# hexapod.net
KiCad netlist of a schematic drawn in EAGLE
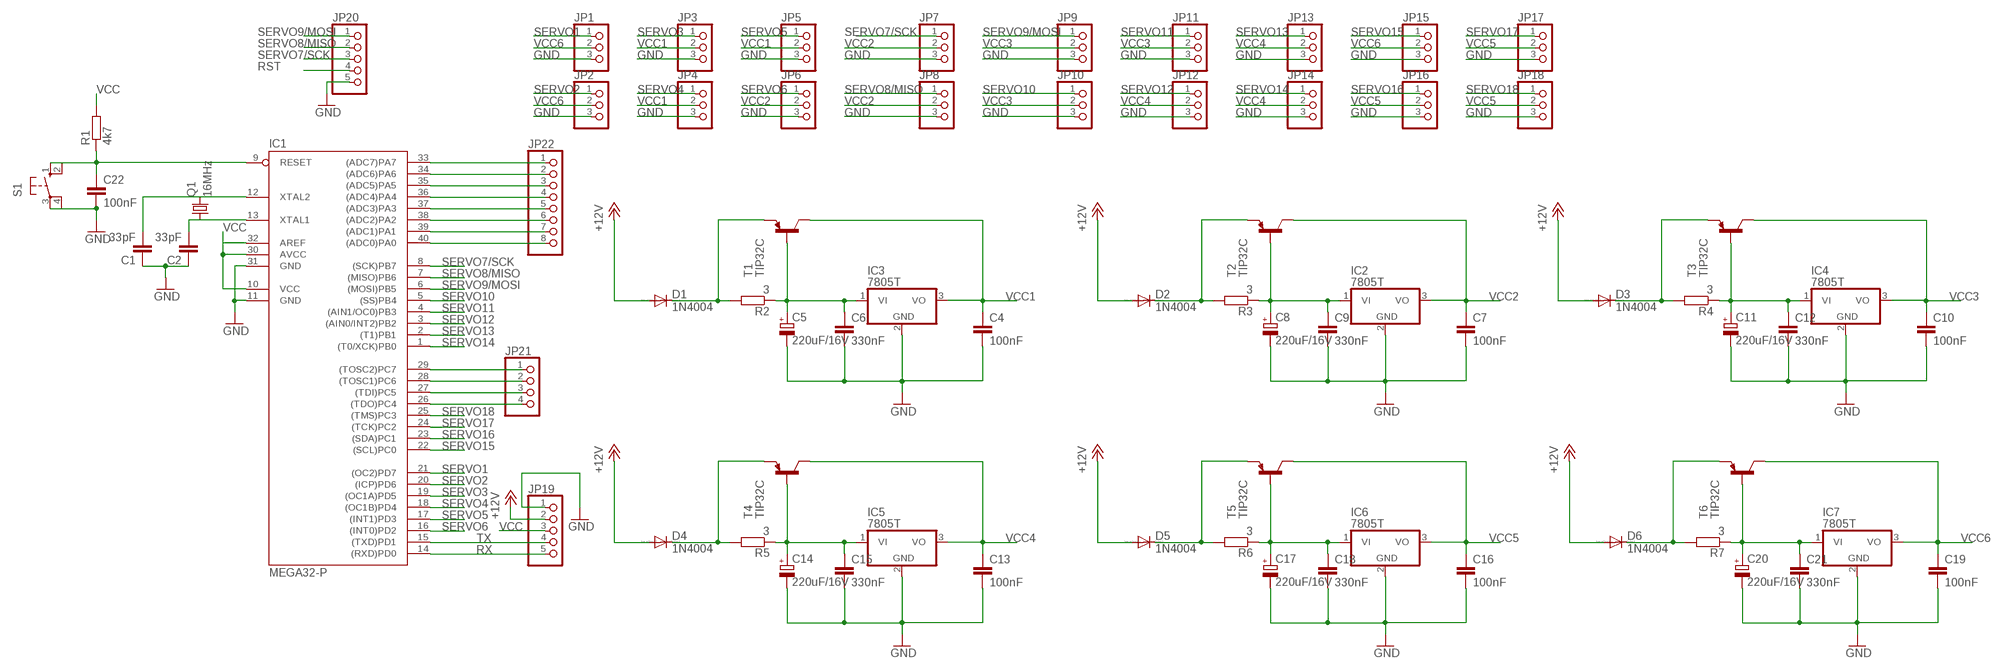
[diagram p0: schematic, sheet 1]

(export (version "E")
  (design (tool "Eeschema 10.0.6"))
  (components
    (comp (ref "C1")
      (value "33pF")
      (footprint "eagle-import:C025-025X050")
      (libsource (lib "eagle-import") (part "resistor_C-EU025-025X050"))
    )
    (comp (ref "C2")
      (value "33pF")
      (footprint "eagle-import:C025-025X050")
      (libsource (lib "eagle-import") (part "resistor_C-EU025-025X050"))
    )
    (comp (ref "C4")
      (value "100nF")
      (footprint "eagle-import:C050-025X075")
      (libsource (lib "eagle-import") (part "C-EU050-025X075"))
    )
    (comp (ref "C5")
      (value "220uF/16V")
      (footprint "eagle-import:E2,5-6E")
      (libsource (lib "eagle-import") (part "CPOL-EUE2,5-6E"))
    )
    (comp (ref "C6")
      (value "330nF")
      (footprint "eagle-import:C050-025X075")
      (libsource (lib "eagle-import") (part "C-EU050-025X075"))
    )
    (comp (ref "C7")
      (value "100nF")
      (footprint "eagle-import:C050-025X075")
      (libsource (lib "eagle-import") (part "C-EU050-025X075"))
    )
    (comp (ref "C8")
      (value "220uF/16V")
      (footprint "eagle-import:E2,5-6E")
      (libsource (lib "eagle-import") (part "CPOL-EUE2,5-6E"))
    )
    (comp (ref "C9")
      (value "330nF")
      (footprint "eagle-import:C050-025X075")
      (libsource (lib "eagle-import") (part "C-EU050-025X075"))
    )
    (comp (ref "C10")
      (value "100nF")
      (footprint "eagle-import:C050-025X075")
      (libsource (lib "eagle-import") (part "C-EU050-025X075"))
    )
    (comp (ref "C11")
      (value "220uF/16V")
      (footprint "eagle-import:E2,5-6E")
      (libsource (lib "eagle-import") (part "CPOL-EUE2,5-6E"))
    )
    (comp (ref "C12")
      (value "330nF")
      (footprint "eagle-import:C050-025X075")
      (libsource (lib "eagle-import") (part "C-EU050-025X075"))
    )
    (comp (ref "C13")
      (value "100nF")
      (footprint "eagle-import:C050-025X075")
      (libsource (lib "eagle-import") (part "C-EU050-025X075"))
    )
    (comp (ref "C14")
      (value "220uF/16V")
      (footprint "eagle-import:E2,5-6E")
      (libsource (lib "eagle-import") (part "CPOL-EUE2,5-6E"))
    )
    (comp (ref "C15")
      (value "330nF")
      (footprint "eagle-import:C050-025X075")
      (libsource (lib "eagle-import") (part "C-EU050-025X075"))
    )
    (comp (ref "C16")
      (value "100nF")
      (footprint "eagle-import:C050-025X075")
      (libsource (lib "eagle-import") (part "C-EU050-025X075"))
    )
    (comp (ref "C17")
      (value "220uF/16V")
      (footprint "eagle-import:E2,5-6E")
      (libsource (lib "eagle-import") (part "CPOL-EUE2,5-6E"))
    )
    (comp (ref "C18")
      (value "330nF")
      (footprint "eagle-import:C050-025X075")
      (libsource (lib "eagle-import") (part "C-EU050-025X075"))
    )
    (comp (ref "C19")
      (value "100nF")
      (footprint "eagle-import:C050-025X075")
      (libsource (lib "eagle-import") (part "C-EU050-025X075"))
    )
    (comp (ref "C20")
      (value "220uF/16V")
      (footprint "eagle-import:E2,5-6E")
      (libsource (lib "eagle-import") (part "CPOL-EUE2,5-6E"))
    )
    (comp (ref "C21")
      (value "330nF")
      (footprint "eagle-import:C050-025X075")
      (libsource (lib "eagle-import") (part "C-EU050-025X075"))
    )
    (comp (ref "C22")
      (value "100nF")
      (footprint "eagle-import:C050-025X075")
      (libsource (lib "eagle-import") (part "C-EU050-025X075"))
    )
    (comp (ref "D1")
      (value "1N4004")
      (footprint "eagle-import:DO41-10")
      (libsource (lib "eagle-import") (part "1N4004"))
    )
    (comp (ref "D2")
      (value "1N4004")
      (footprint "eagle-import:DO41-10")
      (libsource (lib "eagle-import") (part "1N4004"))
    )
    (comp (ref "D3")
      (value "1N4004")
      (footprint "eagle-import:DO41-10")
      (libsource (lib "eagle-import") (part "1N4004"))
    )
    (comp (ref "D4")
      (value "1N4004")
      (footprint "eagle-import:DO41-10")
      (libsource (lib "eagle-import") (part "1N4004"))
    )
    (comp (ref "D5")
      (value "1N4004")
      (footprint "eagle-import:DO41-10")
      (libsource (lib "eagle-import") (part "1N4004"))
    )
    (comp (ref "D6")
      (value "1N4004")
      (footprint "eagle-import:DO41-10")
      (libsource (lib "eagle-import") (part "1N4004"))
    )
    (comp (ref "IC1")
      (value "MEGA32-P")
      (footprint "eagle-import:DIL40")
      (fields (field (name "MPN") "ATMEGA32-16PU"))
      (libsource (lib "eagle-import") (part "MEGA32-P"))
    )
    (comp (ref "IC2")
      (value "7805T")
      (footprint "eagle-import:TO220H")
      (libsource (lib "eagle-import") (part "78T05"))
    )
    (comp (ref "IC3")
      (value "7805T")
      (footprint "eagle-import:TO220H")
      (libsource (lib "eagle-import") (part "78T05"))
    )
    (comp (ref "IC4")
      (value "7805T")
      (footprint "eagle-import:TO220H")
      (libsource (lib "eagle-import") (part "78T05"))
    )
    (comp (ref "IC5")
      (value "7805T")
      (footprint "eagle-import:TO220H")
      (libsource (lib "eagle-import") (part "78T05"))
    )
    (comp (ref "IC6")
      (value "7805T")
      (footprint "eagle-import:TO220H")
      (libsource (lib "eagle-import") (part "78T05"))
    )
    (comp (ref "IC7")
      (value "7805T")
      (footprint "eagle-import:TO220H")
      (libsource (lib "eagle-import") (part "78T05"))
    )
    (comp (ref "JP1")
      (value "PINHD-1X3")
      (footprint "eagle-import:1X03")
      (libsource (lib "eagle-import") (part "PINHD-1X3"))
    )
    (comp (ref "JP2")
      (value "PINHD-1X3")
      (footprint "eagle-import:1X03")
      (libsource (lib "eagle-import") (part "PINHD-1X3"))
    )
    (comp (ref "JP3")
      (value "PINHD-1X3")
      (footprint "eagle-import:1X03")
      (libsource (lib "eagle-import") (part "PINHD-1X3"))
    )
    (comp (ref "JP4")
      (value "PINHD-1X3")
      (footprint "eagle-import:1X03")
      (libsource (lib "eagle-import") (part "PINHD-1X3"))
    )
    (comp (ref "JP5")
      (value "PINHD-1X3")
      (footprint "eagle-import:1X03")
      (libsource (lib "eagle-import") (part "PINHD-1X3"))
    )
    (comp (ref "JP6")
      (value "PINHD-1X3")
      (footprint "eagle-import:1X03")
      (libsource (lib "eagle-import") (part "PINHD-1X3"))
    )
    (comp (ref "JP7")
      (value "PINHD-1X3")
      (footprint "eagle-import:1X03")
      (libsource (lib "eagle-import") (part "PINHD-1X3"))
    )
    (comp (ref "JP8")
      (value "PINHD-1X3")
      (footprint "eagle-import:1X03")
      (libsource (lib "eagle-import") (part "PINHD-1X3"))
    )
    (comp (ref "JP9")
      (value "PINHD-1X3")
      (footprint "eagle-import:1X03")
      (libsource (lib "eagle-import") (part "PINHD-1X3"))
    )
    (comp (ref "JP10")
      (value "PINHD-1X3")
      (footprint "eagle-import:1X03")
      (libsource (lib "eagle-import") (part "PINHD-1X3"))
    )
    (comp (ref "JP11")
      (value "PINHD-1X3")
      (footprint "eagle-import:1X03")
      (libsource (lib "eagle-import") (part "PINHD-1X3"))
    )
    (comp (ref "JP12")
      (value "PINHD-1X3")
      (footprint "eagle-import:1X03")
      (libsource (lib "eagle-import") (part "PINHD-1X3"))
    )
    (comp (ref "JP13")
      (value "PINHD-1X3")
      (footprint "eagle-import:1X03")
      (libsource (lib "eagle-import") (part "PINHD-1X3"))
    )
    (comp (ref "JP14")
      (value "PINHD-1X3")
      (footprint "eagle-import:1X03")
      (libsource (lib "eagle-import") (part "PINHD-1X3"))
    )
    (comp (ref "JP15")
      (value "PINHD-1X3")
      (footprint "eagle-import:1X03")
      (libsource (lib "eagle-import") (part "PINHD-1X3"))
    )
    (comp (ref "JP16")
      (value "PINHD-1X3")
      (footprint "eagle-import:1X03")
      (libsource (lib "eagle-import") (part "PINHD-1X3"))
    )
    (comp (ref "JP17")
      (value "PINHD-1X3")
      (footprint "eagle-import:1X03")
      (libsource (lib "eagle-import") (part "PINHD-1X3"))
    )
    (comp (ref "JP18")
      (value "PINHD-1X3")
      (footprint "eagle-import:1X03")
      (libsource (lib "eagle-import") (part "PINHD-1X3"))
    )
    (comp (ref "JP19")
      (value "PINHD-1X5")
      (footprint "eagle-import:1X05")
      (libsource (lib "eagle-import") (part "PINHD-1X5"))
    )
    (comp (ref "JP20")
      (value "PINHD-1X5")
      (footprint "eagle-import:1X05")
      (libsource (lib "eagle-import") (part "PINHD-1X5"))
    )
    (comp (ref "JP21")
      (value "PINHD-1X4")
      (footprint "eagle-import:1X04")
      (libsource (lib "eagle-import") (part "PINHD-1X4"))
    )
    (comp (ref "JP22")
      (value "PINHD-1X8")
      (footprint "eagle-import:1X08")
      (libsource (lib "eagle-import") (part "PINHD-1X8"))
    )
    (comp (ref "Q1")
      (value "16MHz")
      (footprint "eagle-import:HC49_S")
      (libsource (lib "eagle-import") (part "CRYSTALHC49S"))
    )
    (comp (ref "R1")
      (value "4k7")
      (footprint "eagle-import:0204_7")
      (libsource (lib "eagle-import") (part "R-EU_0204/7"))
    )
    (comp (ref "R2")
      (value "3")
      (footprint "eagle-import:0204_7")
      (libsource (lib "eagle-import") (part "R-EU_0204/7"))
    )
    (comp (ref "R3")
      (value "3")
      (footprint "eagle-import:0204_7")
      (libsource (lib "eagle-import") (part "R-EU_0204/7"))
    )
    (comp (ref "R4")
      (value "3")
      (footprint "eagle-import:0204_7")
      (libsource (lib "eagle-import") (part "R-EU_0204/7"))
    )
    (comp (ref "R5")
      (value "3")
      (footprint "eagle-import:0204_7")
      (libsource (lib "eagle-import") (part "R-EU_0204/7"))
    )
    (comp (ref "R6")
      (value "3")
      (footprint "eagle-import:0204_7")
      (libsource (lib "eagle-import") (part "R-EU_0204/7"))
    )
    (comp (ref "R7")
      (value "3")
      (footprint "eagle-import:0204_7")
      (libsource (lib "eagle-import") (part "R-EU_0204/7"))
    )
    (comp (ref "S1")
      (value "10-XX")
      (footprint "eagle-import:B3F-10XX")
      (fields (field (name "MPN") "B3F-1000"))
      (libsource (lib "eagle-import") (part "10-XX"))
    )
    (comp (ref "T1")
      (value "TIP32C")
      (footprint "eagle-import:TO220")
      (libsource (lib "eagle-import") (part "TIP32C"))
    )
    (comp (ref "T2")
      (value "TIP32C")
      (footprint "eagle-import:TO220")
      (libsource (lib "eagle-import") (part "TIP32C"))
    )
    (comp (ref "T3")
      (value "TIP32C")
      (footprint "eagle-import:TO220")
      (libsource (lib "eagle-import") (part "TIP32C"))
    )
    (comp (ref "T4")
      (value "TIP32C")
      (footprint "eagle-import:TO220")
      (libsource (lib "eagle-import") (part "TIP32C"))
    )
    (comp (ref "T5")
      (value "TIP32C")
      (footprint "eagle-import:TO220")
      (libsource (lib "eagle-import") (part "TIP32C"))
    )
    (comp (ref "T6")
      (value "TIP32C")
      (footprint "eagle-import:TO220")
      (libsource (lib "eagle-import") (part "TIP32C"))
    )
  )
  (nets
    (net (code "1") (name "+12V") (class "Default")
      (node (ref "D1") (pin "A") (pinfunction "A_A") (pintype "passive"))
      (node (ref "D2") (pin "A") (pinfunction "A_A") (pintype "passive"))
      (node (ref "D3") (pin "A") (pinfunction "A_A") (pintype "passive"))
      (node (ref "D4") (pin "A") (pinfunction "A_A") (pintype "passive"))
      (node (ref "D5") (pin "A") (pinfunction "A_A") (pintype "passive"))
      (node (ref "D6") (pin "A") (pinfunction "A_A") (pintype "passive"))
      (node (ref "JP19") (pin "2") (pinfunction "2_2") (pintype "passive"))
    )
    (net (code "2") (name "/RST") (class "Default")
      (node (ref "C22") (pin "1") (pinfunction "1_1") (pintype "passive"))
      (node (ref "IC1") (pin "9") (pinfunction "RESET_9") (pintype "input"))
      (node (ref "JP20") (pin "4") (pinfunction "4_4") (pintype "passive"))
      (node (ref "R1") (pin "1") (pinfunction "1_1") (pintype "passive"))
      (node (ref "S1") (pin "1") (pinfunction "S_1") (pintype "passive"))
      (node (ref "S1") (pin "2") (pinfunction "S1_2") (pintype "passive"))
    )
    (net (code "3") (name "/RX") (class "Default")
      (node (ref "IC1") (pin "14") (pinfunction "(RXD)PD0_14") (pintype "bidirectional"))
      (node (ref "JP19") (pin "5") (pinfunction "5_5") (pintype "passive"))
    )
    (net (code "4") (name "/SERVO1") (class "Default")
      (node (ref "IC1") (pin "21") (pinfunction "(OC2)PD7_21") (pintype "bidirectional"))
      (node (ref "JP1") (pin "1") (pinfunction "1_1") (pintype "passive"))
    )
    (net (code "5") (name "/SERVO2") (class "Default")
      (node (ref "IC1") (pin "20") (pinfunction "(ICP)PD6_20") (pintype "bidirectional"))
      (node (ref "JP2") (pin "1") (pinfunction "1_1") (pintype "passive"))
    )
    (net (code "6") (name "/SERVO3") (class "Default")
      (node (ref "IC1") (pin "19") (pinfunction "(OC1A)PD5_19") (pintype "bidirectional"))
      (node (ref "JP3") (pin "1") (pinfunction "1_1") (pintype "passive"))
    )
    (net (code "7") (name "/SERVO4") (class "Default")
      (node (ref "IC1") (pin "18") (pinfunction "(OC1B)PD4_18") (pintype "bidirectional"))
      (node (ref "JP4") (pin "1") (pinfunction "1_1") (pintype "passive"))
    )
    (net (code "8") (name "/SERVO5") (class "Default")
      (node (ref "IC1") (pin "17") (pinfunction "(INT1)PD3_17") (pintype "bidirectional"))
      (node (ref "JP5") (pin "1") (pinfunction "1_1") (pintype "passive"))
    )
    (net (code "9") (name "/SERVO6") (class "Default")
      (node (ref "IC1") (pin "16") (pinfunction "(INT0)PD2_16") (pintype "bidirectional"))
      (node (ref "JP6") (pin "1") (pinfunction "1_1") (pintype "passive"))
    )
    (net (code "10") (name "/SERVO7{slash}SCK") (class "Default")
      (node (ref "IC1") (pin "8") (pinfunction "(SCK)PB7_8") (pintype "bidirectional"))
      (node (ref "JP20") (pin "3") (pinfunction "3_3") (pintype "passive"))
      (node (ref "JP7") (pin "1") (pinfunction "1_1") (pintype "passive"))
    )
    (net (code "11") (name "/SERVO8{slash}MISO") (class "Default")
      (node (ref "IC1") (pin "7") (pinfunction "(MISO)PB6_7") (pintype "bidirectional"))
      (node (ref "JP20") (pin "2") (pinfunction "2_2") (pintype "passive"))
      (node (ref "JP8") (pin "1") (pinfunction "1_1") (pintype "passive"))
    )
    (net (code "12") (name "/SERVO9{slash}MOSI") (class "Default")
      (node (ref "IC1") (pin "6") (pinfunction "(MOSI)PB5_6") (pintype "bidirectional"))
      (node (ref "JP20") (pin "1") (pinfunction "1_1") (pintype "passive"))
      (node (ref "JP9") (pin "1") (pinfunction "1_1") (pintype "passive"))
    )
    (net (code "13") (name "/SERVO10") (class "Default")
      (node (ref "IC1") (pin "5") (pinfunction "(SS)PB4_5") (pintype "bidirectional"))
      (node (ref "JP10") (pin "1") (pinfunction "1_1") (pintype "passive"))
    )
    (net (code "14") (name "/SERVO11") (class "Default")
      (node (ref "IC1") (pin "4") (pinfunction "(AIN1/OC0)PB3_4") (pintype "bidirectional"))
      (node (ref "JP11") (pin "1") (pinfunction "1_1") (pintype "passive"))
    )
    (net (code "15") (name "/SERVO12") (class "Default")
      (node (ref "IC1") (pin "3") (pinfunction "(AIN0/INT2)PB2_3") (pintype "bidirectional"))
      (node (ref "JP12") (pin "1") (pinfunction "1_1") (pintype "passive"))
    )
    (net (code "16") (name "/SERVO13") (class "Default")
      (node (ref "IC1") (pin "2") (pinfunction "(T1)PB1_2") (pintype "bidirectional"))
      (node (ref "JP13") (pin "1") (pinfunction "1_1") (pintype "passive"))
    )
    (net (code "17") (name "/SERVO14") (class "Default")
      (node (ref "IC1") (pin "1") (pinfunction "(T0/XCK)PB0_1") (pintype "bidirectional"))
      (node (ref "JP14") (pin "1") (pinfunction "1_1") (pintype "passive"))
    )
    (net (code "18") (name "/SERVO15") (class "Default")
      (node (ref "IC1") (pin "22") (pinfunction "(SCL)PC0_22") (pintype "bidirectional"))
      (node (ref "JP15") (pin "1") (pinfunction "1_1") (pintype "passive"))
    )
    (net (code "19") (name "/SERVO16") (class "Default")
      (node (ref "IC1") (pin "23") (pinfunction "(SDA)PC1_23") (pintype "bidirectional"))
      (node (ref "JP16") (pin "1") (pinfunction "1_1") (pintype "passive"))
    )
    (net (code "20") (name "/SERVO17") (class "Default")
      (node (ref "IC1") (pin "24") (pinfunction "(TCK)PC2_24") (pintype "bidirectional"))
      (node (ref "JP17") (pin "1") (pinfunction "1_1") (pintype "passive"))
    )
    (net (code "21") (name "/SERVO18") (class "Default")
      (node (ref "IC1") (pin "25") (pinfunction "(TMS)PC3_25") (pintype "bidirectional"))
      (node (ref "JP18") (pin "1") (pinfunction "1_1") (pintype "passive"))
    )
    (net (code "22") (name "/TX") (class "Default")
      (node (ref "IC1") (pin "15") (pinfunction "(TXD)PD1_15") (pintype "bidirectional"))
      (node (ref "JP19") (pin "4") (pinfunction "4_4") (pintype "passive"))
    )
    (net (code "23") (name "/VCC") (class "Default")
      (node (ref "IC1") (pin "10") (pinfunction "VCC_10") (pintype "power_in"))
      (node (ref "IC1") (pin "30") (pinfunction "AVCC_30") (pintype "power_in"))
      (node (ref "IC1") (pin "32") (pinfunction "AREF_32") (pintype "passive"))
      (node (ref "JP19") (pin "3") (pinfunction "3_3") (pintype "passive"))
      (node (ref "R1") (pin "2") (pinfunction "2_2") (pintype "passive"))
    )
    (net (code "24") (name "/VCC1") (class "Default")
      (node (ref "C4") (pin "1") (pinfunction "1_1") (pintype "passive"))
      (node (ref "IC3") (pin "3") (pinfunction "VO_3") (pintype "passive"))
      (node (ref "JP3") (pin "2") (pinfunction "2_2") (pintype "passive"))
      (node (ref "JP4") (pin "2") (pinfunction "2_2") (pintype "passive"))
      (node (ref "JP5") (pin "2") (pinfunction "2_2") (pintype "passive"))
      (node (ref "T1") (pin "2") (pinfunction "C_2") (pintype "passive"))
    )
    (net (code "25") (name "/VCC2") (class "Default")
      (node (ref "C7") (pin "1") (pinfunction "1_1") (pintype "passive"))
      (node (ref "IC2") (pin "3") (pinfunction "VO_3") (pintype "passive"))
      (node (ref "JP6") (pin "2") (pinfunction "2_2") (pintype "passive"))
      (node (ref "JP7") (pin "2") (pinfunction "2_2") (pintype "passive"))
      (node (ref "JP8") (pin "2") (pinfunction "2_2") (pintype "passive"))
      (node (ref "T2") (pin "2") (pinfunction "C_2") (pintype "passive"))
    )
    (net (code "26") (name "/VCC3") (class "Default")
      (node (ref "C10") (pin "1") (pinfunction "1_1") (pintype "passive"))
      (node (ref "IC4") (pin "3") (pinfunction "VO_3") (pintype "passive"))
      (node (ref "JP10") (pin "2") (pinfunction "2_2") (pintype "passive"))
      (node (ref "JP11") (pin "2") (pinfunction "2_2") (pintype "passive"))
      (node (ref "JP9") (pin "2") (pinfunction "2_2") (pintype "passive"))
      (node (ref "T3") (pin "2") (pinfunction "C_2") (pintype "passive"))
    )
    (net (code "27") (name "/VCC4") (class "Default")
      (node (ref "C13") (pin "1") (pinfunction "1_1") (pintype "passive"))
      (node (ref "IC5") (pin "3") (pinfunction "VO_3") (pintype "passive"))
      (node (ref "JP12") (pin "2") (pinfunction "2_2") (pintype "passive"))
      (node (ref "JP13") (pin "2") (pinfunction "2_2") (pintype "passive"))
      (node (ref "JP14") (pin "2") (pinfunction "2_2") (pintype "passive"))
      (node (ref "T4") (pin "2") (pinfunction "C_2") (pintype "passive"))
    )
    (net (code "28") (name "/VCC5") (class "Default")
      (node (ref "C16") (pin "1") (pinfunction "1_1") (pintype "passive"))
      (node (ref "IC6") (pin "3") (pinfunction "VO_3") (pintype "passive"))
      (node (ref "JP16") (pin "2") (pinfunction "2_2") (pintype "passive"))
      (node (ref "JP17") (pin "2") (pinfunction "2_2") (pintype "passive"))
      (node (ref "JP18") (pin "2") (pinfunction "2_2") (pintype "passive"))
      (node (ref "T5") (pin "2") (pinfunction "C_2") (pintype "passive"))
    )
    (net (code "29") (name "/VCC6") (class "Default")
      (node (ref "C19") (pin "1") (pinfunction "1_1") (pintype "passive"))
      (node (ref "IC7") (pin "3") (pinfunction "VO_3") (pintype "passive"))
      (node (ref "JP1") (pin "2") (pinfunction "2_2") (pintype "passive"))
      (node (ref "JP15") (pin "2") (pinfunction "2_2") (pintype "passive"))
      (node (ref "JP2") (pin "2") (pinfunction "2_2") (pintype "passive"))
      (node (ref "T6") (pin "2") (pinfunction "C_2") (pintype "passive"))
    )
    (net (code "30") (name "GND") (class "Default")
      (node (ref "C1") (pin "1") (pinfunction "1_1") (pintype "passive"))
      (node (ref "C10") (pin "2") (pinfunction "2_2") (pintype "passive"))
      (node (ref "C11") (pin "-") (pinfunction "-_-") (pintype "passive"))
      (node (ref "C12") (pin "2") (pinfunction "2_2") (pintype "passive"))
      (node (ref "C13") (pin "2") (pinfunction "2_2") (pintype "passive"))
      (node (ref "C14") (pin "-") (pinfunction "-_-") (pintype "passive"))
      (node (ref "C15") (pin "2") (pinfunction "2_2") (pintype "passive"))
      (node (ref "C16") (pin "2") (pinfunction "2_2") (pintype "passive"))
      (node (ref "C17") (pin "-") (pinfunction "-_-") (pintype "passive"))
      (node (ref "C18") (pin "2") (pinfunction "2_2") (pintype "passive"))
      (node (ref "C19") (pin "2") (pinfunction "2_2") (pintype "passive"))
      (node (ref "C2") (pin "1") (pinfunction "1_1") (pintype "passive"))
      (node (ref "C20") (pin "-") (pinfunction "-_-") (pintype "passive"))
      (node (ref "C21") (pin "2") (pinfunction "2_2") (pintype "passive"))
      (node (ref "C22") (pin "2") (pinfunction "2_2") (pintype "passive"))
      (node (ref "C4") (pin "2") (pinfunction "2_2") (pintype "passive"))
      (node (ref "C5") (pin "-") (pinfunction "-_-") (pintype "passive"))
      (node (ref "C6") (pin "2") (pinfunction "2_2") (pintype "passive"))
      (node (ref "C7") (pin "2") (pinfunction "2_2") (pintype "passive"))
      (node (ref "C8") (pin "-") (pinfunction "-_-") (pintype "passive"))
      (node (ref "C9") (pin "2") (pinfunction "2_2") (pintype "passive"))
      (node (ref "IC1") (pin "11") (pinfunction "GND_11") (pintype "power_in"))
      (node (ref "IC1") (pin "31") (pinfunction "GND_31") (pintype "power_in"))
      (node (ref "IC2") (pin "2") (pinfunction "GND_2") (pintype "passive"))
      (node (ref "IC3") (pin "2") (pinfunction "GND_2") (pintype "passive"))
      (node (ref "IC4") (pin "2") (pinfunction "GND_2") (pintype "passive"))
      (node (ref "IC5") (pin "2") (pinfunction "GND_2") (pintype "passive"))
      (node (ref "IC6") (pin "2") (pinfunction "GND_2") (pintype "passive"))
      (node (ref "IC7") (pin "2") (pinfunction "GND_2") (pintype "passive"))
      (node (ref "JP1") (pin "3") (pinfunction "3_3") (pintype "passive"))
      (node (ref "JP10") (pin "3") (pinfunction "3_3") (pintype "passive"))
      (node (ref "JP11") (pin "3") (pinfunction "3_3") (pintype "passive"))
      (node (ref "JP12") (pin "3") (pinfunction "3_3") (pintype "passive"))
      (node (ref "JP13") (pin "3") (pinfunction "3_3") (pintype "passive"))
      (node (ref "JP14") (pin "3") (pinfunction "3_3") (pintype "passive"))
      (node (ref "JP15") (pin "3") (pinfunction "3_3") (pintype "passive"))
      (node (ref "JP16") (pin "3") (pinfunction "3_3") (pintype "passive"))
      (node (ref "JP17") (pin "3") (pinfunction "3_3") (pintype "passive"))
      (node (ref "JP18") (pin "3") (pinfunction "3_3") (pintype "passive"))
      (node (ref "JP19") (pin "1") (pinfunction "1_1") (pintype "passive"))
      (node (ref "JP2") (pin "3") (pinfunction "3_3") (pintype "passive"))
      (node (ref "JP20") (pin "5") (pinfunction "5_5") (pintype "passive"))
      (node (ref "JP3") (pin "3") (pinfunction "3_3") (pintype "passive"))
      (node (ref "JP4") (pin "3") (pinfunction "3_3") (pintype "passive"))
      (node (ref "JP5") (pin "3") (pinfunction "3_3") (pintype "passive"))
      (node (ref "JP6") (pin "3") (pinfunction "3_3") (pintype "passive"))
      (node (ref "JP7") (pin "3") (pinfunction "3_3") (pintype "passive"))
      (node (ref "JP8") (pin "3") (pinfunction "3_3") (pintype "passive"))
      (node (ref "JP9") (pin "3") (pinfunction "3_3") (pintype "passive"))
      (node (ref "S1") (pin "3") (pinfunction "P_3") (pintype "passive"))
      (node (ref "S1") (pin "4") (pinfunction "P1_4") (pintype "passive"))
    )
    (net (code "31") (name "Net-(IC1-(ADC0)PA0)") (class "Default")
      (node (ref "IC1") (pin "40") (pinfunction "(ADC0)PA0_40") (pintype "bidirectional"))
      (node (ref "JP22") (pin "8") (pinfunction "8_8") (pintype "passive"))
    )
    (net (code "32") (name "Net-(IC1-(ADC1)PA1)") (class "Default")
      (node (ref "IC1") (pin "39") (pinfunction "(ADC1)PA1_39") (pintype "bidirectional"))
      (node (ref "JP22") (pin "7") (pinfunction "7_7") (pintype "passive"))
    )
    (net (code "33") (name "Net-(IC1-(ADC2)PA2)") (class "Default")
      (node (ref "IC1") (pin "38") (pinfunction "(ADC2)PA2_38") (pintype "bidirectional"))
      (node (ref "JP22") (pin "6") (pinfunction "6_6") (pintype "passive"))
    )
    (net (code "34") (name "Net-(IC1-(ADC3)PA3)") (class "Default")
      (node (ref "IC1") (pin "37") (pinfunction "(ADC3)PA3_37") (pintype "bidirectional"))
      (node (ref "JP22") (pin "5") (pinfunction "5_5") (pintype "passive"))
    )
    (net (code "35") (name "Net-(IC1-(ADC4)PA4)") (class "Default")
      (node (ref "IC1") (pin "36") (pinfunction "(ADC4)PA4_36") (pintype "bidirectional"))
      (node (ref "JP22") (pin "4") (pinfunction "4_4") (pintype "passive"))
    )
    (net (code "36") (name "Net-(IC1-(ADC5)PA5)") (class "Default")
      (node (ref "IC1") (pin "35") (pinfunction "(ADC5)PA5_35") (pintype "bidirectional"))
      (node (ref "JP22") (pin "3") (pinfunction "3_3") (pintype "passive"))
    )
    (net (code "37") (name "Net-(IC1-(ADC6)PA6)") (class "Default")
      (node (ref "IC1") (pin "34") (pinfunction "(ADC6)PA6_34") (pintype "bidirectional"))
      (node (ref "JP22") (pin "2") (pinfunction "2_2") (pintype "passive"))
    )
    (net (code "38") (name "Net-(IC1-(ADC7)PA7)") (class "Default")
      (node (ref "IC1") (pin "33") (pinfunction "(ADC7)PA7_33") (pintype "bidirectional"))
      (node (ref "JP22") (pin "1") (pinfunction "1_1") (pintype "passive"))
    )
    (net (code "39") (name "Net-(IC1-(TDI)PC5)") (class "Default")
      (node (ref "IC1") (pin "27") (pinfunction "(TDI)PC5_27") (pintype "bidirectional"))
      (node (ref "JP21") (pin "3") (pinfunction "3_3") (pintype "passive"))
    )
    (net (code "40") (name "Net-(IC1-(TDO)PC4)") (class "Default")
      (node (ref "IC1") (pin "26") (pinfunction "(TDO)PC4_26") (pintype "bidirectional"))
      (node (ref "JP21") (pin "4") (pinfunction "4_4") (pintype "passive"))
    )
    (net (code "41") (name "Net-(IC1-(TOSC1)PC6)") (class "Default")
      (node (ref "IC1") (pin "28") (pinfunction "(TOSC1)PC6_28") (pintype "bidirectional"))
      (node (ref "JP21") (pin "2") (pinfunction "2_2") (pintype "passive"))
    )
    (net (code "42") (name "Net-(IC1-(TOSC2)PC7)") (class "Default")
      (node (ref "IC1") (pin "29") (pinfunction "(TOSC2)PC7_29") (pintype "bidirectional"))
      (node (ref "JP21") (pin "1") (pinfunction "1_1") (pintype "passive"))
    )
    (net (code "43") (name "Net-(IC1-XTAL1)") (class "Default")
      (node (ref "C2") (pin "2") (pinfunction "2_2") (pintype "passive"))
      (node (ref "IC1") (pin "13") (pinfunction "XTAL1_13") (pintype "bidirectional"))
      (node (ref "Q1") (pin "1") (pinfunction "1_1") (pintype "passive"))
    )
    (net (code "44") (name "Net-(IC1-XTAL2)") (class "Default")
      (node (ref "C1") (pin "2") (pinfunction "2_2") (pintype "passive"))
      (node (ref "IC1") (pin "12") (pinfunction "XTAL2_12") (pintype "bidirectional"))
      (node (ref "Q1") (pin "2") (pinfunction "2_2") (pintype "passive"))
    )
    (net (code "45") (name "Net-(IC2-VI)") (class "Default")
      (node (ref "C8") (pin "+") (pinfunction "+_+") (pintype "passive"))
      (node (ref "C9") (pin "1") (pinfunction "1_1") (pintype "passive"))
      (node (ref "IC2") (pin "1") (pinfunction "VI_1") (pintype "input"))
      (node (ref "R3") (pin "1") (pinfunction "1_1") (pintype "passive"))
      (node (ref "T2") (pin "1") (pinfunction "B_1") (pintype "passive"))
    )
    (net (code "46") (name "Net-(IC3-VI)") (class "Default")
      (node (ref "C5") (pin "+") (pinfunction "+_+") (pintype "passive"))
      (node (ref "C6") (pin "1") (pinfunction "1_1") (pintype "passive"))
      (node (ref "IC3") (pin "1") (pinfunction "VI_1") (pintype "input"))
      (node (ref "R2") (pin "1") (pinfunction "1_1") (pintype "passive"))
      (node (ref "T1") (pin "1") (pinfunction "B_1") (pintype "passive"))
    )
    (net (code "47") (name "Net-(IC4-VI)") (class "Default")
      (node (ref "C11") (pin "+") (pinfunction "+_+") (pintype "passive"))
      (node (ref "C12") (pin "1") (pinfunction "1_1") (pintype "passive"))
      (node (ref "IC4") (pin "1") (pinfunction "VI_1") (pintype "input"))
      (node (ref "R4") (pin "1") (pinfunction "1_1") (pintype "passive"))
      (node (ref "T3") (pin "1") (pinfunction "B_1") (pintype "passive"))
    )
    (net (code "48") (name "Net-(IC5-VI)") (class "Default")
      (node (ref "C14") (pin "+") (pinfunction "+_+") (pintype "passive"))
      (node (ref "C15") (pin "1") (pinfunction "1_1") (pintype "passive"))
      (node (ref "IC5") (pin "1") (pinfunction "VI_1") (pintype "input"))
      (node (ref "R5") (pin "1") (pinfunction "1_1") (pintype "passive"))
      (node (ref "T4") (pin "1") (pinfunction "B_1") (pintype "passive"))
    )
    (net (code "49") (name "Net-(IC6-VI)") (class "Default")
      (node (ref "C17") (pin "+") (pinfunction "+_+") (pintype "passive"))
      (node (ref "C18") (pin "1") (pinfunction "1_1") (pintype "passive"))
      (node (ref "IC6") (pin "1") (pinfunction "VI_1") (pintype "input"))
      (node (ref "R6") (pin "1") (pinfunction "1_1") (pintype "passive"))
      (node (ref "T5") (pin "1") (pinfunction "B_1") (pintype "passive"))
    )
    (net (code "50") (name "Net-(IC7-VI)") (class "Default")
      (node (ref "C20") (pin "+") (pinfunction "+_+") (pintype "passive"))
      (node (ref "C21") (pin "1") (pinfunction "1_1") (pintype "passive"))
      (node (ref "IC7") (pin "1") (pinfunction "VI_1") (pintype "input"))
      (node (ref "R7") (pin "1") (pinfunction "1_1") (pintype "passive"))
      (node (ref "T6") (pin "1") (pinfunction "B_1") (pintype "passive"))
    )
    (net (code "51") (name "Net-(T1-E)") (class "Default")
      (node (ref "D1") (pin "C") (pinfunction "C_C") (pintype "passive"))
      (node (ref "R2") (pin "2") (pinfunction "2_2") (pintype "passive"))
      (node (ref "T1") (pin "3") (pinfunction "E_3") (pintype "passive"))
    )
    (net (code "52") (name "Net-(T2-E)") (class "Default")
      (node (ref "D2") (pin "C") (pinfunction "C_C") (pintype "passive"))
      (node (ref "R3") (pin "2") (pinfunction "2_2") (pintype "passive"))
      (node (ref "T2") (pin "3") (pinfunction "E_3") (pintype "passive"))
    )
    (net (code "53") (name "Net-(T3-E)") (class "Default")
      (node (ref "D3") (pin "C") (pinfunction "C_C") (pintype "passive"))
      (node (ref "R4") (pin "2") (pinfunction "2_2") (pintype "passive"))
      (node (ref "T3") (pin "3") (pinfunction "E_3") (pintype "passive"))
    )
    (net (code "54") (name "Net-(T4-E)") (class "Default")
      (node (ref "D4") (pin "C") (pinfunction "C_C") (pintype "passive"))
      (node (ref "R5") (pin "2") (pinfunction "2_2") (pintype "passive"))
      (node (ref "T4") (pin "3") (pinfunction "E_3") (pintype "passive"))
    )
    (net (code "55") (name "Net-(T5-E)") (class "Default")
      (node (ref "D5") (pin "C") (pinfunction "C_C") (pintype "passive"))
      (node (ref "R6") (pin "2") (pinfunction "2_2") (pintype "passive"))
      (node (ref "T5") (pin "3") (pinfunction "E_3") (pintype "passive"))
    )
    (net (code "56") (name "Net-(T6-E)") (class "Default")
      (node (ref "D6") (pin "C") (pinfunction "C_C") (pintype "passive"))
      (node (ref "R7") (pin "2") (pinfunction "2_2") (pintype "passive"))
      (node (ref "T6") (pin "3") (pinfunction "E_3") (pintype "passive"))
    )
  )
)
